# Wheatstone.net
KiCad netlist of a schematic drawn in EAGLE
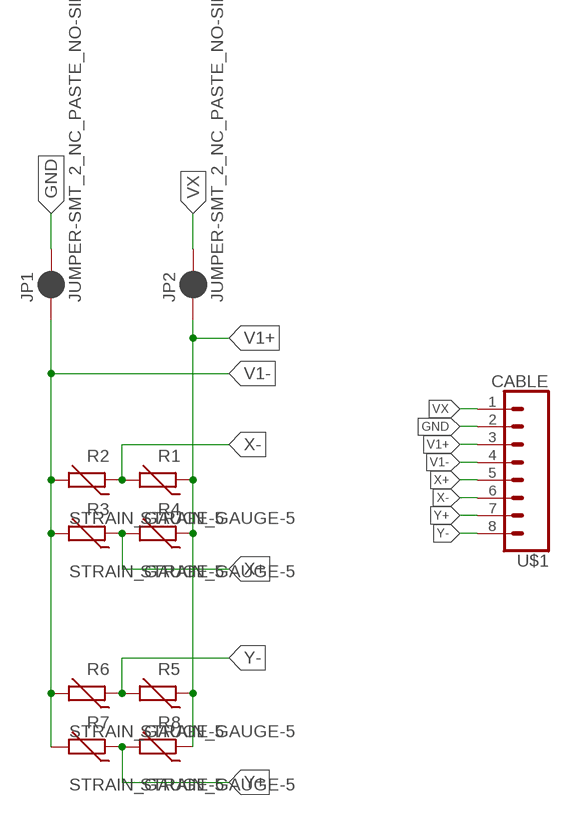
[diagram p0: schematic, sheet 1]

(export (version "E")
  (design (tool "Eeschema 10.0.6"))
  (components
    (comp (ref "JP1")
      (value "JUMPER-SMT_2_NC_PASTE_NO-SILK")
      (footprint "eagle-import:SMT-JUMPER_2_NC_PASTE_NO-SILK")
      (libsource (lib "eagle-import") (part "JUMPER-SMT_2_NC_PASTE_NO-SILK"))
    )
    (comp (ref "JP2")
      (value "JUMPER-SMT_2_NC_PASTE_NO-SILK")
      (footprint "eagle-import:SMT-JUMPER_2_NC_PASTE_NO-SILK")
      (libsource (lib "eagle-import") (part "JUMPER-SMT_2_NC_PASTE_NO-SILK"))
    )
    (comp (ref "R1")
      (value "STRAIN_GAUGE-5")
      (footprint "eagle-import:STRAIN_GAUGE")
      (libsource (lib "eagle-import") (part "STRAIN_GAUGE-5"))
    )
    (comp (ref "R2")
      (value "STRAIN_GAUGE-5")
      (footprint "eagle-import:STRAIN_GAUGE")
      (libsource (lib "eagle-import") (part "STRAIN_GAUGE-5"))
    )
    (comp (ref "R3")
      (value "STRAIN_GAUGE-5")
      (footprint "eagle-import:STRAIN_GAUGE")
      (libsource (lib "eagle-import") (part "STRAIN_GAUGE-5"))
    )
    (comp (ref "R4")
      (value "STRAIN_GAUGE-5")
      (footprint "eagle-import:STRAIN_GAUGE")
      (libsource (lib "eagle-import") (part "STRAIN_GAUGE-5"))
    )
    (comp (ref "R5")
      (value "STRAIN_GAUGE-5")
      (footprint "eagle-import:STRAIN_GAUGE")
      (libsource (lib "eagle-import") (part "STRAIN_GAUGE-5"))
    )
    (comp (ref "R6")
      (value "STRAIN_GAUGE-5")
      (footprint "eagle-import:STRAIN_GAUGE")
      (libsource (lib "eagle-import") (part "STRAIN_GAUGE-5"))
    )
    (comp (ref "R7")
      (value "STRAIN_GAUGE-5")
      (footprint "eagle-import:STRAIN_GAUGE")
      (libsource (lib "eagle-import") (part "STRAIN_GAUGE-5"))
    )
    (comp (ref "R8")
      (value "STRAIN_GAUGE-5")
      (footprint "eagle-import:STRAIN_GAUGE")
      (libsource (lib "eagle-import") (part "STRAIN_GAUGE-5"))
    )
    (comp (ref "U$1")
      (value "CABLE")
      (footprint "eagle-import:CABLE")
      (libsource (lib "eagle-import") (part "CABLE"))
    )
  )
  (nets
    (net (code "1") (name "GND") (class "Default")
      (node (ref "JP1") (pin "2") (pinfunction "2_2") (pintype "passive"))
      (node (ref "U$1") (pin "2") (pinfunction "2_2") (pintype "passive"))
    )
    (net (code "2") (name "V1+") (class "Default")
      (node (ref "JP2") (pin "1") (pinfunction "1_1") (pintype "passive"))
      (node (ref "R1") (pin "1") (pinfunction "1_1") (pintype "passive"))
      (node (ref "R4") (pin "1") (pinfunction "1_1") (pintype "passive"))
      (node (ref "R5") (pin "1") (pinfunction "1_1") (pintype "passive"))
      (node (ref "R8") (pin "1") (pinfunction "1_1") (pintype "passive"))
      (node (ref "U$1") (pin "3") (pinfunction "3_3") (pintype "passive"))
    )
    (net (code "3") (name "V1-") (class "Default")
      (node (ref "JP1") (pin "1") (pinfunction "1_1") (pintype "passive"))
      (node (ref "R2") (pin "2") (pinfunction "2_2") (pintype "passive"))
      (node (ref "R3") (pin "2") (pinfunction "2_2") (pintype "passive"))
      (node (ref "R6") (pin "2") (pinfunction "2_2") (pintype "passive"))
      (node (ref "R7") (pin "2") (pinfunction "2_2") (pintype "passive"))
      (node (ref "U$1") (pin "4") (pinfunction "4_4") (pintype "passive"))
    )
    (net (code "4") (name "VX") (class "Default")
      (node (ref "JP2") (pin "2") (pinfunction "2_2") (pintype "passive"))
      (node (ref "U$1") (pin "1") (pinfunction "1_1") (pintype "passive"))
    )
    (net (code "5") (name "X+") (class "Default")
      (node (ref "R3") (pin "1") (pinfunction "1_1") (pintype "passive"))
      (node (ref "R4") (pin "2") (pinfunction "2_2") (pintype "passive"))
      (node (ref "U$1") (pin "5") (pinfunction "5_5") (pintype "passive"))
    )
    (net (code "6") (name "X-") (class "Default")
      (node (ref "R1") (pin "2") (pinfunction "2_2") (pintype "passive"))
      (node (ref "R2") (pin "1") (pinfunction "1_1") (pintype "passive"))
      (node (ref "U$1") (pin "6") (pinfunction "6_6") (pintype "passive"))
    )
    (net (code "7") (name "Y+") (class "Default")
      (node (ref "R7") (pin "1") (pinfunction "1_1") (pintype "passive"))
      (node (ref "R8") (pin "2") (pinfunction "2_2") (pintype "passive"))
      (node (ref "U$1") (pin "7") (pinfunction "7_7") (pintype "passive"))
    )
    (net (code "8") (name "Y-") (class "Default")
      (node (ref "R5") (pin "2") (pinfunction "2_2") (pintype "passive"))
      (node (ref "R6") (pin "1") (pinfunction "1_1") (pintype "passive"))
      (node (ref "U$1") (pin "8") (pinfunction "8_8") (pintype "passive"))
    )
  )
)
